# INPUT_POWER.net
KiCad netlist of a schematic drawn in Altium Designer
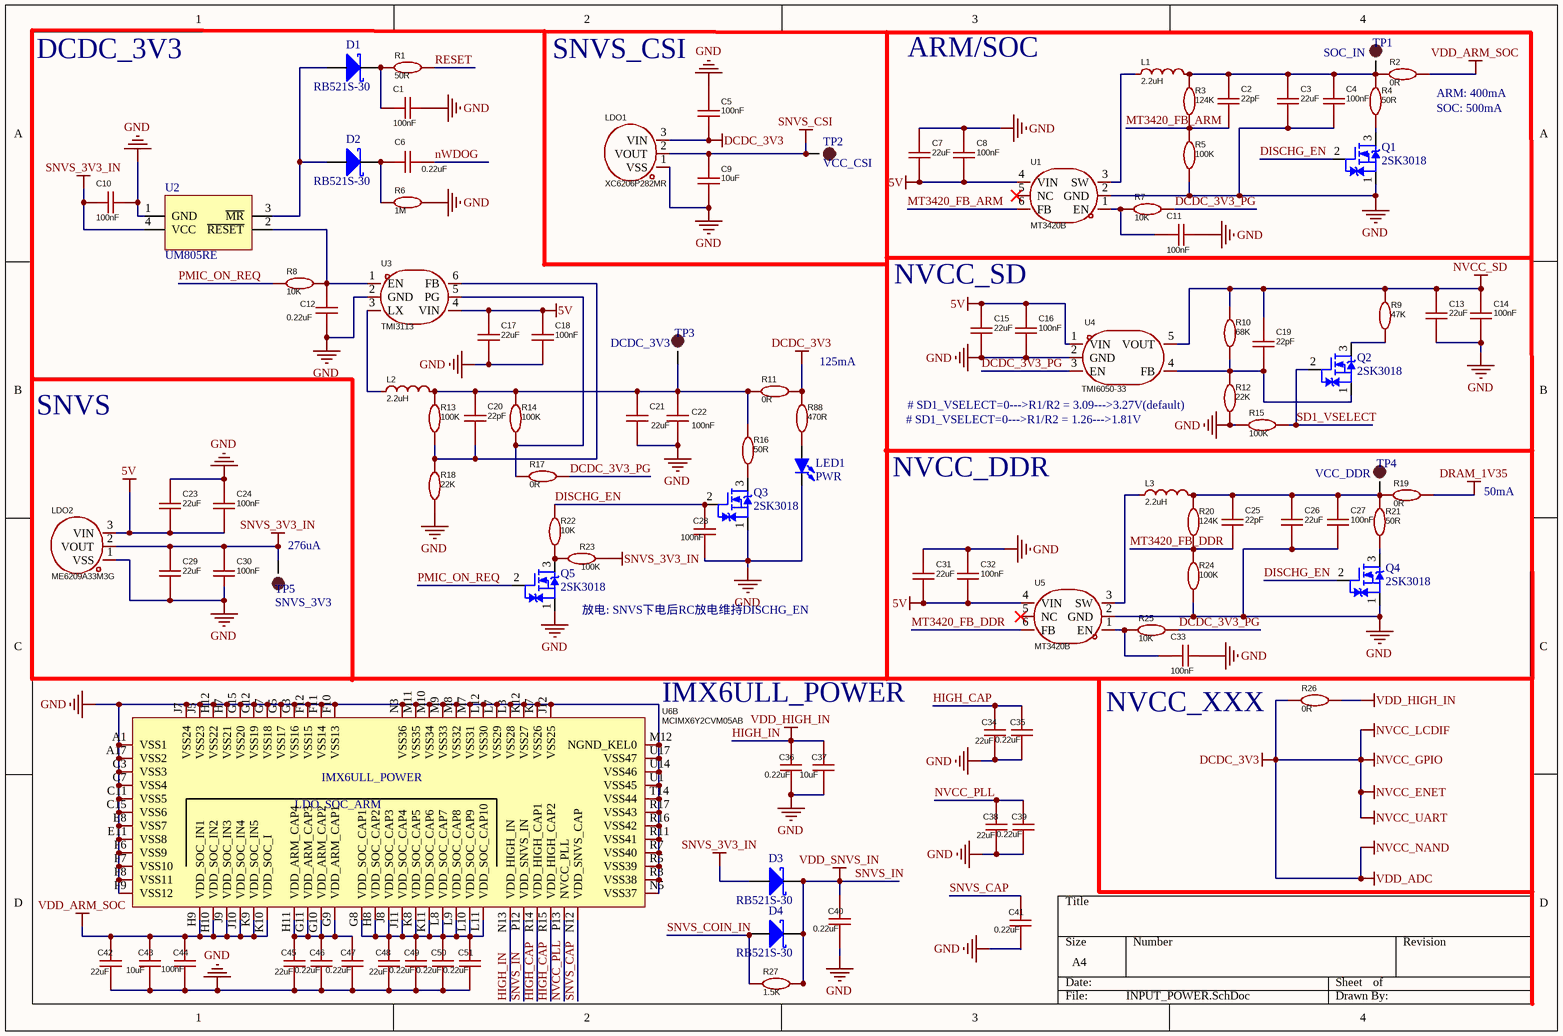
[diagram p0: INPUT_POWER.SchDoc]

(export (version "E")
  (design (tool "Eeschema 10.0.6"))
  (components
    (comp (ref "C1")
      (value "100nF")
      (footprint "PcbLib1:C0402")
      (description "容值:100nF;精度:±10%;额定电压:50V;材质(温度系数):X7R;")
      (fields
        (field (name "MANUFACTURER") "muRata(村田)")
        (field (name "MANUFACTURER PART") "GRM155R71H104KE14D")
      )
      (libsource (lib "Schlib1") (part "C0402"))
    )
    (comp (ref "C2")
      (value "22pF")
      (footprint "PcbLib1:C0402")
      (description "容值:100nF;精度:±10%;额定电压:50V;材质(温度系数):X7R;")
      (fields
        (field (name "MANUFACTURER") "muRata(村田)")
        (field (name "MANUFACTURER PART") "GRM155R71H104KE14D")
      )
      (libsource (lib "Schlib1") (part "C0402"))
    )
    (comp (ref "C3")
      (value "22uF")
      (footprint "PcbLib1:C0603")
      (description "容值:22uF;精度:±20%;额定电压:10V;材质(温度系数):X5R;")
      (fields
        (field (name "MANUFACTURER") "Chinocera(华瓷)")
        (field (name "MANUFACTURER PART") "HGC0603R5226M100NTHJ")
      )
      (libsource (lib "Schlib1") (part "C0603"))
    )
    (comp (ref "C4")
      (value "100nF")
      (footprint "PcbLib1:C0402")
      (description "容值:100nF;精度:±10%;额定电压:50V;材质(温度系数):X7R;")
      (fields
        (field (name "MANUFACTURER") "muRata(村田)")
        (field (name "MANUFACTURER PART") "GRM155R71H104KE14D")
      )
      (libsource (lib "Schlib1") (part "C0402"))
    )
    (comp (ref "C5")
      (value "100nF")
      (footprint "PcbLib1:C0402")
      (description "容值:100nF;精度:±10%;额定电压:50V;材质(温度系数):X7R;")
      (fields
        (field (name "MANUFACTURER") "muRata(村田)")
        (field (name "MANUFACTURER PART") "GRM155R71H104KE14D")
      )
      (libsource (lib "Schlib1") (part "C0402"))
    )
    (comp (ref "C6")
      (value "0.22uF")
      (footprint "PcbLib1:C0402")
      (description "容值:100nF;精度:±10%;额定电压:50V;材质(温度系数):X7R;")
      (fields
        (field (name "MANUFACTURER") "muRata(村田)")
        (field (name "MANUFACTURER PART") "GRM155R71H104KE14D")
      )
      (libsource (lib "Schlib1") (part "C0402"))
    )
    (comp (ref "C7")
      (value "22uF")
      (footprint "PcbLib1:C0603")
      (description "容值:22uF;精度:±20%;额定电压:10V;材质(温度系数):X5R;")
      (fields
        (field (name "MANUFACTURER") "Chinocera(华瓷)")
        (field (name "MANUFACTURER PART") "HGC0603R5226M100NTHJ")
      )
      (libsource (lib "Schlib1") (part "C0603"))
    )
    (comp (ref "C8")
      (value "100nF")
      (footprint "PcbLib1:C0402")
      (description "容值:100nF;精度:±10%;额定电压:50V;材质(温度系数):X7R;")
      (fields
        (field (name "MANUFACTURER") "muRata(村田)")
        (field (name "MANUFACTURER PART") "GRM155R71H104KE14D")
      )
      (libsource (lib "Schlib1") (part "C0402"))
    )
    (comp (ref "C9")
      (value "10uF")
      (footprint "PcbLib1:C0402")
      (description "容值:100nF;精度:±10%;额定电压:50V;材质(温度系数):X7R;")
      (fields
        (field (name "MANUFACTURER") "muRata(村田)")
        (field (name "MANUFACTURER PART") "GRM155R71H104KE14D")
      )
      (libsource (lib "Schlib1") (part "C0402"))
    )
    (comp (ref "C10")
      (value "100nF")
      (footprint "PcbLib1:C0402")
      (description "容值:100nF;精度:±10%;额定电压:50V;材质(温度系数):X7R;")
      (fields
        (field (name "MANUFACTURER") "muRata(村田)")
        (field (name "MANUFACTURER PART") "GRM155R71H104KE14D")
      )
      (libsource (lib "Schlib1") (part "C0402"))
    )
    (comp (ref "C11")
      (value "100nF")
      (footprint "PcbLib1:C0402")
      (description "容值:100nF;精度:±10%;额定电压:50V;材质(温度系数):X7R;")
      (fields
        (field (name "MANUFACTURER") "muRata(村田)")
        (field (name "MANUFACTURER PART") "GRM155R71H104KE14D")
      )
      (libsource (lib "Schlib1") (part "C0402"))
    )
    (comp (ref "C12")
      (value "0.22uF")
      (footprint "PcbLib1:C0402")
      (description "容值:100nF;精度:±10%;额定电压:50V;材质(温度系数):X7R;")
      (fields
        (field (name "MANUFACTURER") "muRata(村田)")
        (field (name "MANUFACTURER PART") "GRM155R71H104KE14D")
      )
      (libsource (lib "Schlib1") (part "C0402"))
    )
    (comp (ref "C13")
      (value "22uF")
      (footprint "PcbLib1:C0603")
      (description "容值:22uF;精度:±20%;额定电压:10V;材质(温度系数):X5R;")
      (fields
        (field (name "MANUFACTURER") "Chinocera(华瓷)")
        (field (name "MANUFACTURER PART") "HGC0603R5226M100NTHJ")
      )
      (libsource (lib "Schlib1") (part "C0603"))
    )
    (comp (ref "C14")
      (value "100nF")
      (footprint "PcbLib1:C0402")
      (description "容值:100nF;精度:±10%;额定电压:50V;材质(温度系数):X7R;")
      (fields
        (field (name "MANUFACTURER") "muRata(村田)")
        (field (name "MANUFACTURER PART") "GRM155R71H104KE14D")
      )
      (libsource (lib "Schlib1") (part "C0402"))
    )
    (comp (ref "C15")
      (value "22uF")
      (footprint "PcbLib1:C0603")
      (description "容值:22uF;精度:±20%;额定电压:10V;材质(温度系数):X5R;")
      (fields
        (field (name "MANUFACTURER") "Chinocera(华瓷)")
        (field (name "MANUFACTURER PART") "HGC0603R5226M100NTHJ")
      )
      (libsource (lib "Schlib1") (part "C0603"))
    )
    (comp (ref "C16")
      (value "100nF")
      (footprint "PcbLib1:C0402")
      (description "容值:100nF;精度:±10%;额定电压:50V;材质(温度系数):X7R;")
      (fields
        (field (name "MANUFACTURER") "muRata(村田)")
        (field (name "MANUFACTURER PART") "GRM155R71H104KE14D")
      )
      (libsource (lib "Schlib1") (part "C0402"))
    )
    (comp (ref "C17")
      (value "22uF")
      (footprint "PcbLib1:C0603")
      (description "容值:22uF;精度:±20%;额定电压:10V;材质(温度系数):X5R;")
      (fields
        (field (name "MANUFACTURER") "Chinocera(华瓷)")
        (field (name "MANUFACTURER PART") "HGC0603R5226M100NTHJ")
      )
      (libsource (lib "Schlib1") (part "C0603"))
    )
    (comp (ref "C18")
      (value "100nF")
      (footprint "PcbLib1:C0402")
      (description "容值:100nF;精度:±10%;额定电压:50V;材质(温度系数):X7R;")
      (fields
        (field (name "MANUFACTURER") "muRata(村田)")
        (field (name "MANUFACTURER PART") "GRM155R71H104KE14D")
      )
      (libsource (lib "Schlib1") (part "C0402"))
    )
    (comp (ref "C19")
      (value "22pF")
      (footprint "PcbLib1:C0402")
      (description "容值:100nF;精度:±10%;额定电压:50V;材质(温度系数):X7R;")
      (fields
        (field (name "MANUFACTURER") "muRata(村田)")
        (field (name "MANUFACTURER PART") "GRM155R71H104KE14D")
      )
      (libsource (lib "Schlib1") (part "C0402"))
    )
    (comp (ref "C20")
      (value "22pF")
      (footprint "PcbLib1:C0402")
      (description "容值:100nF;精度:±10%;额定电压:50V;材质(温度系数):X7R;")
      (fields
        (field (name "MANUFACTURER") "muRata(村田)")
        (field (name "MANUFACTURER PART") "GRM155R71H104KE14D")
      )
      (libsource (lib "Schlib1") (part "C0402"))
    )
    (comp (ref "C21")
      (value "22uF")
      (footprint "PcbLib1:C0603")
      (description "容值:22uF;精度:±20%;额定电压:10V;材质(温度系数):X5R;")
      (fields
        (field (name "MANUFACTURER") "Chinocera(华瓷)")
        (field (name "MANUFACTURER PART") "HGC0603R5226M100NTHJ")
      )
      (libsource (lib "Schlib1") (part "C0603"))
    )
    (comp (ref "C22")
      (value "100nF")
      (footprint "PcbLib1:C0402")
      (description "容值:100nF;精度:±10%;额定电压:50V;材质(温度系数):X7R;")
      (fields
        (field (name "MANUFACTURER") "muRata(村田)")
        (field (name "MANUFACTURER PART") "GRM155R71H104KE14D")
      )
      (libsource (lib "Schlib1") (part "C0402"))
    )
    (comp (ref "C23")
      (value "22uF")
      (footprint "PcbLib1:C0603")
      (description "容值:22uF;精度:±20%;额定电压:10V;材质(温度系数):X5R;")
      (fields
        (field (name "MANUFACTURER") "Chinocera(华瓷)")
        (field (name "MANUFACTURER PART") "HGC0603R5226M100NTHJ")
      )
      (libsource (lib "Schlib1") (part "C0603"))
    )
    (comp (ref "C24")
      (value "100nF")
      (footprint "PcbLib1:C0402")
      (description "容值:100nF;精度:±10%;额定电压:50V;材质(温度系数):X7R;")
      (fields
        (field (name "MANUFACTURER") "muRata(村田)")
        (field (name "MANUFACTURER PART") "GRM155R71H104KE14D")
      )
      (libsource (lib "Schlib1") (part "C0402"))
    )
    (comp (ref "C25")
      (value "22pF")
      (footprint "PcbLib1:C0402")
      (description "容值:100nF;精度:±10%;额定电压:50V;材质(温度系数):X7R;")
      (fields
        (field (name "MANUFACTURER") "muRata(村田)")
        (field (name "MANUFACTURER PART") "GRM155R71H104KE14D")
      )
      (libsource (lib "Schlib1") (part "C0402"))
    )
    (comp (ref "C26")
      (value "22uF")
      (footprint "PcbLib1:C0603")
      (description "容值:22uF;精度:±20%;额定电压:10V;材质(温度系数):X5R;")
      (fields
        (field (name "MANUFACTURER") "Chinocera(华瓷)")
        (field (name "MANUFACTURER PART") "HGC0603R5226M100NTHJ")
      )
      (libsource (lib "Schlib1") (part "C0603"))
    )
    (comp (ref "C27")
      (value "100nF")
      (footprint "PcbLib1:C0402")
      (description "容值:100nF;精度:±10%;额定电压:50V;材质(温度系数):X7R;")
      (fields
        (field (name "MANUFACTURER") "muRata(村田)")
        (field (name "MANUFACTURER PART") "GRM155R71H104KE14D")
      )
      (libsource (lib "Schlib1") (part "C0402"))
    )
    (comp (ref "C28")
      (value "100nF")
      (footprint "PcbLib1:C0402")
      (description "容值:100nF;精度:±10%;额定电压:50V;材质(温度系数):X7R;")
      (fields
        (field (name "MANUFACTURER") "muRata(村田)")
        (field (name "MANUFACTURER PART") "GRM155R71H104KE14D")
      )
      (libsource (lib "Schlib1") (part "C0402"))
    )
    (comp (ref "C29")
      (value "22uF")
      (footprint "PcbLib1:C0603")
      (description "容值:22uF;精度:±20%;额定电压:10V;材质(温度系数):X5R;")
      (fields
        (field (name "MANUFACTURER") "Chinocera(华瓷)")
        (field (name "MANUFACTURER PART") "HGC0603R5226M100NTHJ")
      )
      (libsource (lib "Schlib1") (part "C0603"))
    )
    (comp (ref "C30")
      (value "100nF")
      (footprint "PcbLib1:C0402")
      (description "容值:100nF;精度:±10%;额定电压:50V;材质(温度系数):X7R;")
      (fields
        (field (name "MANUFACTURER") "muRata(村田)")
        (field (name "MANUFACTURER PART") "GRM155R71H104KE14D")
      )
      (libsource (lib "Schlib1") (part "C0402"))
    )
    (comp (ref "C31")
      (value "22uF")
      (footprint "PcbLib1:C0603")
      (description "容值:22uF;精度:±20%;额定电压:10V;材质(温度系数):X5R;")
      (fields
        (field (name "MANUFACTURER") "Chinocera(华瓷)")
        (field (name "MANUFACTURER PART") "HGC0603R5226M100NTHJ")
      )
      (libsource (lib "Schlib1") (part "C0603"))
    )
    (comp (ref "C32")
      (value "100nF")
      (footprint "PcbLib1:C0402")
      (description "容值:100nF;精度:±10%;额定电压:50V;材质(温度系数):X7R;")
      (fields
        (field (name "MANUFACTURER") "muRata(村田)")
        (field (name "MANUFACTURER PART") "GRM155R71H104KE14D")
      )
      (libsource (lib "Schlib1") (part "C0402"))
    )
    (comp (ref "C33")
      (value "100nF")
      (footprint "PcbLib1:C0402")
      (description "容值:100nF;精度:±10%;额定电压:50V;材质(温度系数):X7R;")
      (fields
        (field (name "MANUFACTURER") "muRata(村田)")
        (field (name "MANUFACTURER PART") "GRM155R71H104KE14D")
      )
      (libsource (lib "Schlib1") (part "C0402"))
    )
    (comp (ref "C34")
      (value "22uF")
      (footprint "PcbLib1:C0603")
      (description "容值:22uF;精度:±20%;额定电压:10V;材质(温度系数):X5R;")
      (fields
        (field (name "MANUFACTURER") "Chinocera(华瓷)")
        (field (name "MANUFACTURER PART") "HGC0603R5226M100NTHJ")
      )
      (libsource (lib "Schlib1") (part "C0603"))
    )
    (comp (ref "C35")
      (value "0.22uF")
      (footprint "PcbLib1:C0402")
      (description "容值:100nF;精度:±10%;额定电压:50V;材质(温度系数):X7R;")
      (fields
        (field (name "MANUFACTURER") "muRata(村田)")
        (field (name "MANUFACTURER PART") "GRM155R71H104KE14D")
      )
      (libsource (lib "Schlib1") (part "C0402"))
    )
    (comp (ref "C36")
      (value "0.22uF")
      (footprint "PcbLib1:C0402")
      (description "容值:100nF;精度:±10%;额定电压:50V;材质(温度系数):X7R;")
      (fields
        (field (name "MANUFACTURER") "muRata(村田)")
        (field (name "MANUFACTURER PART") "GRM155R71H104KE14D")
      )
      (libsource (lib "Schlib1") (part "C0402"))
    )
    (comp (ref "C37")
      (value "10uF")
      (footprint "PcbLib1:C0402")
      (description "容值:100nF;精度:±10%;额定电压:50V;材质(温度系数):X7R;")
      (fields
        (field (name "MANUFACTURER") "muRata(村田)")
        (field (name "MANUFACTURER PART") "GRM155R71H104KE14D")
      )
      (libsource (lib "Schlib1") (part "C0402"))
    )
    (comp (ref "C38")
      (value "22uF")
      (footprint "PcbLib1:C0603")
      (description "容值:22uF;精度:±20%;额定电压:10V;材质(温度系数):X5R;")
      (fields
        (field (name "MANUFACTURER") "Chinocera(华瓷)")
        (field (name "MANUFACTURER PART") "HGC0603R5226M100NTHJ")
      )
      (libsource (lib "Schlib1") (part "C0603"))
    )
    (comp (ref "C39")
      (value "0.22uF")
      (footprint "PcbLib1:C0402")
      (description "容值:100nF;精度:±10%;额定电压:50V;材质(温度系数):X7R;")
      (fields
        (field (name "MANUFACTURER") "muRata(村田)")
        (field (name "MANUFACTURER PART") "GRM155R71H104KE14D")
      )
      (libsource (lib "Schlib1") (part "C0402"))
    )
    (comp (ref "C40")
      (value "0.22uF")
      (footprint "PcbLib1:C0402")
      (description "容值:100nF;精度:±10%;额定电压:50V;材质(温度系数):X7R;")
      (fields
        (field (name "MANUFACTURER") "muRata(村田)")
        (field (name "MANUFACTURER PART") "GRM155R71H104KE14D")
      )
      (libsource (lib "Schlib1") (part "C0402"))
    )
    (comp (ref "C41")
      (value "0.22uF")
      (footprint "PcbLib1:C0402")
      (description "容值:100nF;精度:±10%;额定电压:50V;材质(温度系数):X7R;")
      (fields
        (field (name "MANUFACTURER") "muRata(村田)")
        (field (name "MANUFACTURER PART") "GRM155R71H104KE14D")
      )
      (libsource (lib "Schlib1") (part "C0402"))
    )
    (comp (ref "C42")
      (value "22uF")
      (footprint "PcbLib1:C0603")
      (description "容值:22uF;精度:±20%;额定电压:10V;材质(温度系数):X5R;")
      (fields
        (field (name "MANUFACTURER") "Chinocera(华瓷)")
        (field (name "MANUFACTURER PART") "HGC0603R5226M100NTHJ")
      )
      (libsource (lib "Schlib1") (part "C0603"))
    )
    (comp (ref "C43")
      (value "10uF")
      (footprint "PcbLib1:C0402")
      (description "容值:100nF;精度:±10%;额定电压:50V;材质(温度系数):X7R;")
      (fields
        (field (name "MANUFACTURER") "muRata(村田)")
        (field (name "MANUFACTURER PART") "GRM155R71H104KE14D")
      )
      (libsource (lib "Schlib1") (part "C0402"))
    )
    (comp (ref "C44")
      (value "100nF")
      (footprint "PcbLib1:C0402")
      (description "容值:100nF;精度:±10%;额定电压:50V;材质(温度系数):X7R;")
      (fields
        (field (name "MANUFACTURER") "muRata(村田)")
        (field (name "MANUFACTURER PART") "GRM155R71H104KE14D")
      )
      (libsource (lib "Schlib1") (part "C0402"))
    )
    (comp (ref "C45")
      (value "22uF")
      (footprint "PcbLib1:C0603")
      (description "容值:22uF;精度:±20%;额定电压:10V;材质(温度系数):X5R;")
      (fields
        (field (name "MANUFACTURER") "Chinocera(华瓷)")
        (field (name "MANUFACTURER PART") "HGC0603R5226M100NTHJ")
      )
      (libsource (lib "Schlib1") (part "C0603"))
    )
    (comp (ref "C46")
      (value "0.22uF")
      (footprint "PcbLib1:C0402")
      (description "容值:100nF;精度:±10%;额定电压:50V;材质(温度系数):X7R;")
      (fields
        (field (name "MANUFACTURER") "muRata(村田)")
        (field (name "MANUFACTURER PART") "GRM155R71H104KE14D")
      )
      (libsource (lib "Schlib1") (part "C0402"))
    )
    (comp (ref "C47")
      (value "0.22uF")
      (footprint "PcbLib1:C0402")
      (description "容值:100nF;精度:±10%;额定电压:50V;材质(温度系数):X7R;")
      (fields
        (field (name "MANUFACTURER") "muRata(村田)")
        (field (name "MANUFACTURER PART") "GRM155R71H104KE14D")
      )
      (libsource (lib "Schlib1") (part "C0402"))
    )
    (comp (ref "C48")
      (value "22uF")
      (footprint "PcbLib1:C0603")
      (description "容值:22uF;精度:±20%;额定电压:10V;材质(温度系数):X5R;")
      (fields
        (field (name "MANUFACTURER") "Chinocera(华瓷)")
        (field (name "MANUFACTURER PART") "HGC0603R5226M100NTHJ")
      )
      (libsource (lib "Schlib1") (part "C0603"))
    )
    (comp (ref "C49")
      (value "0.22uF")
      (footprint "PcbLib1:C0402")
      (description "容值:100nF;精度:±10%;额定电压:50V;材质(温度系数):X7R;")
      (fields
        (field (name "MANUFACTURER") "muRata(村田)")
        (field (name "MANUFACTURER PART") "GRM155R71H104KE14D")
      )
      (libsource (lib "Schlib1") (part "C0402"))
    )
    (comp (ref "C50")
      (value "0.22uF")
      (footprint "PcbLib1:C0402")
      (description "容值:100nF;精度:±10%;额定电压:50V;材质(温度系数):X7R;")
      (fields
        (field (name "MANUFACTURER") "muRata(村田)")
        (field (name "MANUFACTURER PART") "GRM155R71H104KE14D")
      )
      (libsource (lib "Schlib1") (part "C0402"))
    )
    (comp (ref "C51")
      (value "0.22uF")
      (footprint "PcbLib1:C0402")
      (description "容值:100nF;精度:±10%;额定电压:50V;材质(温度系数):X7R;")
      (fields
        (field (name "MANUFACTURER") "muRata(村田)")
        (field (name "MANUFACTURER PART") "GRM155R71H104KE14D")
      )
      (libsource (lib "Schlib1") (part "C0402"))
    )
    (comp (ref "D1") (value "RB521S-30") (footprint "SOD-523") (libsource (lib "Schlib1") (part "RB521S-30")))
    (comp (ref "D2") (value "RB521S-30") (footprint "SOD-523") (libsource (lib "Schlib1") (part "RB521S-30")))
    (comp (ref "D3") (value "RB521S-30") (footprint "SOD-523") (libsource (lib "Schlib1") (part "RB521S-30")))
    (comp (ref "D4") (value "RB521S-30") (footprint "SOD-523") (libsource (lib "Schlib1") (part "RB521S-30")))
    (comp (ref "L1")
      (value "2.2uH")
      (footprint "PcbLib1:IND-SMD_L2.5-W2.0_MHCHL2520")
      (description "电感值:2.2uH;精度:±20%;额定电流:3A;饱和电流(Isat):3.8A;类型:一体成型电感;")
      (fields
        (field (name "MANUFACTURER") "cjiang(长江微电)")
        (field (name "MANUFACTURER PART") "FTC252012S2R2MBCA")
      )
      (libsource (lib "Schlib1") (part "L2.5_SMD"))
    )
    (comp (ref "L2")
      (value "2.2uH")
      (footprint "PcbLib1:IND-SMD_L2.5-W2.0_MHCHL2520")
      (description "电感值:2.2uH;精度:±20%;额定电流:3A;饱和电流(Isat):3.8A;类型:一体成型电感;")
      (fields
        (field (name "MANUFACTURER") "cjiang(长江微电)")
        (field (name "MANUFACTURER PART") "FTC252012S2R2MBCA")
      )
      (libsource (lib "Schlib1") (part "L2.5_SMD"))
    )
    (comp (ref "L3")
      (value "2.2uH")
      (footprint "PcbLib1:IND-SMD_L2.5-W2.0_MHCHL2520")
      (description "电感值:2.2uH;精度:±20%;额定电流:3A;饱和电流(Isat):3.8A;类型:一体成型电感;")
      (fields
        (field (name "MANUFACTURER") "cjiang(长江微电)")
        (field (name "MANUFACTURER PART") "FTC252012S2R2MBCA")
      )
      (libsource (lib "Schlib1") (part "L2.5_SMD"))
    )
    (comp (ref "LDO1")
      (value "XC6206P282MR")
      (footprint "PcbLib1:SOT-23-3_L2.9-W1.6-P1.90-LS2.8-BR")
      (description "输出类型:固定;最大输入电压:6V;输出电压:3.3V;最大输出电流:250mA;电源纹波抑制比(PSRR):-;输出极性:正极;")
      (fields (field (name "MANUFACTURER") "MICRONE(南京微盟)") (field (name "MANUFACTURER PART") "ME6209A33M3G"))
      (libsource (lib "Schlib1") (part "XC6206P282MR"))
    )
    (comp (ref "LDO2")
      (value "ME6209A33M3G")
      (footprint "PcbLib1:SOT-23-3_L2.9-W1.6-P1.90-LS2.8-BR")
      (description "输出类型:固定;最大输入电压:18V;输出电压:3.3V;最大输出电流:250mA;电源纹波抑制比(PSRR):-;输出极性:正极;")
      (fields (field (name "MANUFACTURER") "MICRONE(南京微盟)"))
      (libsource (lib "Schlib1") (part "ME6209A33M3G"))
    )
    (comp (ref "LED1")
      (value "PWR")
      (footprint "PcbLib1:LED 0603B")
      (description "贴片LED")
      (fields (field (name "版权归属") "源创客"))
      (libsource (lib "Schlib1") (part "LED-SMD"))
    )
    (comp (ref "Q1")
      (value "2SK3018")
      (footprint "SOT:SC70-3N")
      (description "N沟场效应管  30V,0.1A")
      (fields (field (name "版权归属") "源创客"))
      (libsource (lib "Schlib1") (part "2SK3018"))
    )
    (comp (ref "Q2")
      (value "2SK3018")
      (footprint "SOT:SC70-3N")
      (description "N沟场效应管  30V,0.1A")
      (fields (field (name "版权归属") "源创客"))
      (libsource (lib "Schlib1") (part "2SK3018"))
    )
    (comp (ref "Q3")
      (value "2SK3018")
      (footprint "SOT:SC70-3N")
      (description "N沟场效应管  30V,0.1A")
      (fields (field (name "版权归属") "源创客"))
      (libsource (lib "Schlib1") (part "2SK3018"))
    )
    (comp (ref "Q4")
      (value "2SK3018")
      (footprint "SOT:SC70-3N")
      (description "N沟场效应管  30V,0.1A")
      (fields (field (name "版权归属") "源创客"))
      (libsource (lib "Schlib1") (part "2SK3018"))
    )
    (comp (ref "Q5")
      (value "2SK3018")
      (footprint "SOT:SC70-3N")
      (description "N沟场效应管  30V,0.1A")
      (fields (field (name "版权归属") "源创客"))
      (libsource (lib "Schlib1") (part "2SK3018"))
    )
    (comp (ref "R1")
      (value "50R")
      (footprint "PcbLib1:R0402")
      (description "电阻类型:厚膜电阻;阻值:1kΩ;精度:±1%;功率:62.5mW;最大工作电压:50V;温度系数:±100ppm/℃;")
      (fields
        (field (name "MANUFACTURER") "UNI-ROYAL(厚声)")
        (field (name "MANUFACTURER PART") "0402WGF1001TCE")
      )
      (libsource (lib "Schlib1") (part "R0402"))
    )
    (comp (ref "R2")
      (value "0R")
      (footprint "PcbLib1:R0402")
      (description "电阻类型:厚膜电阻;阻值:1kΩ;精度:±1%;功率:62.5mW;最大工作电压:50V;温度系数:±100ppm/℃;")
      (fields
        (field (name "MANUFACTURER") "UNI-ROYAL(厚声)")
        (field (name "MANUFACTURER PART") "0402WGF1001TCE")
      )
      (libsource (lib "Schlib1") (part "R0402"))
    )
    (comp (ref "R3")
      (value "124K")
      (footprint "PcbLib1:R0402")
      (description "电阻类型:厚膜电阻;阻值:1kΩ;精度:±1%;功率:62.5mW;最大工作电压:50V;温度系数:±100ppm/℃;")
      (fields
        (field (name "MANUFACTURER") "UNI-ROYAL(厚声)")
        (field (name "MANUFACTURER PART") "0402WGF1001TCE")
      )
      (libsource (lib "Schlib1") (part "R0402"))
    )
    (comp (ref "R4")
      (value "50R")
      (footprint "PcbLib1:R0402")
      (description "电阻类型:厚膜电阻;阻值:1kΩ;精度:±1%;功率:62.5mW;最大工作电压:50V;温度系数:±100ppm/℃;")
      (fields
        (field (name "MANUFACTURER") "UNI-ROYAL(厚声)")
        (field (name "MANUFACTURER PART") "0402WGF1001TCE")
      )
      (libsource (lib "Schlib1") (part "R0402"))
    )
    (comp (ref "R5")
      (value "100K")
      (footprint "PcbLib1:R0402")
      (description "电阻类型:厚膜电阻;阻值:1kΩ;精度:±1%;功率:62.5mW;最大工作电压:50V;温度系数:±100ppm/℃;")
      (fields
        (field (name "MANUFACTURER") "UNI-ROYAL(厚声)")
        (field (name "MANUFACTURER PART") "0402WGF1001TCE")
      )
      (libsource (lib "Schlib1") (part "R0402"))
    )
    (comp (ref "R6")
      (value "1M")
      (footprint "PcbLib1:R0402")
      (description "电阻类型:厚膜电阻;阻值:1kΩ;精度:±1%;功率:62.5mW;最大工作电压:50V;温度系数:±100ppm/℃;")
      (fields
        (field (name "MANUFACTURER") "UNI-ROYAL(厚声)")
        (field (name "MANUFACTURER PART") "0402WGF1001TCE")
      )
      (libsource (lib "Schlib1") (part "R0402"))
    )
    (comp (ref "R7")
      (value "10K")
      (footprint "PcbLib1:R0402")
      (description "电阻类型:厚膜电阻;阻值:1kΩ;精度:±1%;功率:62.5mW;最大工作电压:50V;温度系数:±100ppm/℃;")
      (fields
        (field (name "MANUFACTURER") "UNI-ROYAL(厚声)")
        (field (name "MANUFACTURER PART") "0402WGF1001TCE")
      )
      (libsource (lib "Schlib1") (part "R0402"))
    )
    (comp (ref "R8")
      (value "10K")
      (footprint "PcbLib1:R0402")
      (description "电阻类型:厚膜电阻;阻值:1kΩ;精度:±1%;功率:62.5mW;最大工作电压:50V;温度系数:±100ppm/℃;")
      (fields
        (field (name "MANUFACTURER") "UNI-ROYAL(厚声)")
        (field (name "MANUFACTURER PART") "0402WGF1001TCE")
      )
      (libsource (lib "Schlib1") (part "R0402"))
    )
    (comp (ref "R9")
      (value "47K")
      (footprint "PcbLib1:R0402")
      (description "电阻类型:厚膜电阻;阻值:1kΩ;精度:±1%;功率:62.5mW;最大工作电压:50V;温度系数:±100ppm/℃;")
      (fields
        (field (name "MANUFACTURER") "UNI-ROYAL(厚声)")
        (field (name "MANUFACTURER PART") "0402WGF1001TCE")
      )
      (libsource (lib "Schlib1") (part "R0402"))
    )
    (comp (ref "R10")
      (value "68K")
      (footprint "PcbLib1:R0402")
      (description "电阻类型:厚膜电阻;阻值:1kΩ;精度:±1%;功率:62.5mW;最大工作电压:50V;温度系数:±100ppm/℃;")
      (fields
        (field (name "MANUFACTURER") "UNI-ROYAL(厚声)")
        (field (name "MANUFACTURER PART") "0402WGF1001TCE")
      )
      (libsource (lib "Schlib1") (part "R0402"))
    )
    (comp (ref "R11")
      (value "0R")
      (footprint "PcbLib1:R0402")
      (description "电阻类型:厚膜电阻;阻值:1kΩ;精度:±1%;功率:62.5mW;最大工作电压:50V;温度系数:±100ppm/℃;")
      (fields
        (field (name "MANUFACTURER") "UNI-ROYAL(厚声)")
        (field (name "MANUFACTURER PART") "0402WGF1001TCE")
      )
      (libsource (lib "Schlib1") (part "R0402"))
    )
    (comp (ref "R12")
      (value "22K")
      (footprint "PcbLib1:R0402")
      (description "电阻类型:厚膜电阻;阻值:1kΩ;精度:±1%;功率:62.5mW;最大工作电压:50V;温度系数:±100ppm/℃;")
      (fields
        (field (name "MANUFACTURER") "UNI-ROYAL(厚声)")
        (field (name "MANUFACTURER PART") "0402WGF1001TCE")
      )
      (libsource (lib "Schlib1") (part "R0402"))
    )
    (comp (ref "R13")
      (value "100K")
      (footprint "PcbLib1:R0402")
      (description "电阻类型:厚膜电阻;阻值:1kΩ;精度:±1%;功率:62.5mW;最大工作电压:50V;温度系数:±100ppm/℃;")
      (fields
        (field (name "MANUFACTURER") "UNI-ROYAL(厚声)")
        (field (name "MANUFACTURER PART") "0402WGF1001TCE")
      )
      (libsource (lib "Schlib1") (part "R0402"))
    )
    (comp (ref "R14")
      (value "100K")
      (footprint "PcbLib1:R0402")
      (description "电阻类型:厚膜电阻;阻值:1kΩ;精度:±1%;功率:62.5mW;最大工作电压:50V;温度系数:±100ppm/℃;")
      (fields
        (field (name "MANUFACTURER") "UNI-ROYAL(厚声)")
        (field (name "MANUFACTURER PART") "0402WGF1001TCE")
      )
      (libsource (lib "Schlib1") (part "R0402"))
    )
    (comp (ref "R15")
      (value "100K")
      (footprint "PcbLib1:R0402")
      (description "电阻类型:厚膜电阻;阻值:1kΩ;精度:±1%;功率:62.5mW;最大工作电压:50V;温度系数:±100ppm/℃;")
      (fields
        (field (name "MANUFACTURER") "UNI-ROYAL(厚声)")
        (field (name "MANUFACTURER PART") "0402WGF1001TCE")
      )
      (libsource (lib "Schlib1") (part "R0402"))
    )
    (comp (ref "R16")
      (value "50R")
      (footprint "PcbLib1:R0402")
      (description "电阻类型:厚膜电阻;阻值:1kΩ;精度:±1%;功率:62.5mW;最大工作电压:50V;温度系数:±100ppm/℃;")
      (fields
        (field (name "MANUFACTURER") "UNI-ROYAL(厚声)")
        (field (name "MANUFACTURER PART") "0402WGF1001TCE")
      )
      (libsource (lib "Schlib1") (part "R0402"))
    )
    (comp (ref "R17")
      (value "0R")
      (footprint "PcbLib1:R0402")
      (description "电阻类型:厚膜电阻;阻值:1kΩ;精度:±1%;功率:62.5mW;最大工作电压:50V;温度系数:±100ppm/℃;")
      (fields
        (field (name "MANUFACTURER") "UNI-ROYAL(厚声)")
        (field (name "MANUFACTURER PART") "0402WGF1001TCE")
      )
      (libsource (lib "Schlib1") (part "R0402"))
    )
    (comp (ref "R18")
      (value "22K")
      (footprint "PcbLib1:R0402")
      (description "电阻类型:厚膜电阻;阻值:1kΩ;精度:±1%;功率:62.5mW;最大工作电压:50V;温度系数:±100ppm/℃;")
      (fields
        (field (name "MANUFACTURER") "UNI-ROYAL(厚声)")
        (field (name "MANUFACTURER PART") "0402WGF1001TCE")
      )
      (libsource (lib "Schlib1") (part "R0402"))
    )
    (comp (ref "R19")
      (value "0R")
      (footprint "PcbLib1:R0402")
      (description "电阻类型:厚膜电阻;阻值:1kΩ;精度:±1%;功率:62.5mW;最大工作电压:50V;温度系数:±100ppm/℃;")
      (fields
        (field (name "MANUFACTURER") "UNI-ROYAL(厚声)")
        (field (name "MANUFACTURER PART") "0402WGF1001TCE")
      )
      (libsource (lib "Schlib1") (part "R0402"))
    )
    (comp (ref "R20")
      (value "124K")
      (footprint "PcbLib1:R0402")
      (description "电阻类型:厚膜电阻;阻值:1kΩ;精度:±1%;功率:62.5mW;最大工作电压:50V;温度系数:±100ppm/℃;")
      (fields
        (field (name "MANUFACTURER") "UNI-ROYAL(厚声)")
        (field (name "MANUFACTURER PART") "0402WGF1001TCE")
      )
      (libsource (lib "Schlib1") (part "R0402"))
    )
    (comp (ref "R21")
      (value "50R")
      (footprint "PcbLib1:R0402")
      (description "电阻类型:厚膜电阻;阻值:1kΩ;精度:±1%;功率:62.5mW;最大工作电压:50V;温度系数:±100ppm/℃;")
      (fields
        (field (name "MANUFACTURER") "UNI-ROYAL(厚声)")
        (field (name "MANUFACTURER PART") "0402WGF1001TCE")
      )
      (libsource (lib "Schlib1") (part "R0402"))
    )
    (comp (ref "R22")
      (value "10K")
      (footprint "PcbLib1:R0402")
      (description "电阻类型:厚膜电阻;阻值:1kΩ;精度:±1%;功率:62.5mW;最大工作电压:50V;温度系数:±100ppm/℃;")
      (fields
        (field (name "MANUFACTURER") "UNI-ROYAL(厚声)")
        (field (name "MANUFACTURER PART") "0402WGF1001TCE")
      )
      (libsource (lib "Schlib1") (part "R0402"))
    )
    (comp (ref "R23")
      (value "100K")
      (footprint "PcbLib1:R0402")
      (description "电阻类型:厚膜电阻;阻值:1kΩ;精度:±1%;功率:62.5mW;最大工作电压:50V;温度系数:±100ppm/℃;")
      (fields
        (field (name "MANUFACTURER") "UNI-ROYAL(厚声)")
        (field (name "MANUFACTURER PART") "0402WGF1001TCE")
      )
      (libsource (lib "Schlib1") (part "R0402"))
    )
    (comp (ref "R24")
      (value "100K")
      (footprint "PcbLib1:R0402")
      (description "电阻类型:厚膜电阻;阻值:1kΩ;精度:±1%;功率:62.5mW;最大工作电压:50V;温度系数:±100ppm/℃;")
      (fields
        (field (name "MANUFACTURER") "UNI-ROYAL(厚声)")
        (field (name "MANUFACTURER PART") "0402WGF1001TCE")
      )
      (libsource (lib "Schlib1") (part "R0402"))
    )
    (comp (ref "R25")
      (value "10K")
      (footprint "PcbLib1:R0402")
      (description "电阻类型:厚膜电阻;阻值:1kΩ;精度:±1%;功率:62.5mW;最大工作电压:50V;温度系数:±100ppm/℃;")
      (fields
        (field (name "MANUFACTURER") "UNI-ROYAL(厚声)")
        (field (name "MANUFACTURER PART") "0402WGF1001TCE")
      )
      (libsource (lib "Schlib1") (part "R0402"))
    )
    (comp (ref "R26")
      (value "0R")
      (footprint "PcbLib1:R0402")
      (description "电阻类型:厚膜电阻;阻值:1kΩ;精度:±1%;功率:62.5mW;最大工作电压:50V;温度系数:±100ppm/℃;")
      (fields
        (field (name "MANUFACTURER") "UNI-ROYAL(厚声)")
        (field (name "MANUFACTURER PART") "0402WGF1001TCE")
      )
      (libsource (lib "Schlib1") (part "R0402"))
    )
    (comp (ref "R27")
      (value "1.5K")
      (footprint "PcbLib1:R0402")
      (description "电阻类型:厚膜电阻;阻值:1kΩ;精度:±1%;功率:62.5mW;最大工作电压:50V;温度系数:±100ppm/℃;")
      (fields
        (field (name "MANUFACTURER") "UNI-ROYAL(厚声)")
        (field (name "MANUFACTURER PART") "0402WGF1001TCE")
      )
      (libsource (lib "Schlib1") (part "R0402"))
    )
    (comp (ref "R88")
      (value "470R")
      (footprint "PcbLib1:R0402")
      (description "电阻类型:厚膜电阻;阻值:1kΩ;精度:±1%;功率:62.5mW;最大工作电压:50V;温度系数:±100ppm/℃;")
      (fields
        (field (name "MANUFACTURER") "UNI-ROYAL(厚声)")
        (field (name "MANUFACTURER PART") "0402WGF1001TCE")
      )
      (libsource (lib "Schlib1") (part "R0402"))
    )
    (comp (ref "TP1")
      (value "SOC_IN")
      (footprint "TP-1.0")
      (description "测试点")
      (libsource (lib "Schlib1") (part "TEST-POINT"))
    )
    (comp (ref "TP2")
      (value "VCC_CSI")
      (footprint "TP-1.0")
      (description "测试点")
      (libsource (lib "Schlib1") (part "TEST-POINT"))
    )
    (comp (ref "TP3")
      (value "DCDC_3V3")
      (footprint "TP-1.0")
      (description "测试点")
      (libsource (lib "Schlib1") (part "TEST-POINT"))
    )
    (comp (ref "TP4")
      (value "VCC_DDR")
      (footprint "TP-1.0")
      (description "测试点")
      (libsource (lib "Schlib1") (part "TEST-POINT"))
    )
    (comp (ref "TP5")
      (value "SNVS_3V3")
      (footprint "TP-1.0")
      (description "测试点")
      (libsource (lib "Schlib1") (part "TEST-POINT"))
    )
    (comp (ref "U1")
      (value "MT3420B")
      (footprint "PcbLib1:SOT-23-6_L2.9-W1.6-P0.95-LS2.8-BL")
      (description "功能类型:降压型;输出类型:可调;输入电压:2.3V~6V;输出电流:2A;")
      (fields (field (name "MANUFACTURER") "西安航天民芯"))
      (libsource (lib "Schlib1") (part "MT3420B"))
    )
    (comp (ref "U2") (value "UM805RE") (footprint "SOT143") (libsource (lib "Schlib1") (part "UM805RE")))
    (comp (ref "U3")
      (value "TMI3113")
      (footprint "PcbLib1:SOT-23-6_L2.9-W1.6-P0.95-LS2.8-BL")
      (fields (field (name "MANUFACTURER") "TMI(拓尔微)"))
      (libsource (lib "Schlib1") (part "TMI3113"))
    )
    (comp (ref "U4")
      (value "TMI6050-33")
      (footprint "PcbLib1:SOT-23-5_L2.9-W1.6-P0.95-LS2.8-BR")
      (description "输出类型:-;")
      (fields (field (name "MANUFACTURER") "TMI(拓尔微)"))
      (libsource (lib "Schlib1") (part "TMI6050-33"))
    )
    (comp (ref "U5")
      (value "MT3420B")
      (footprint "PcbLib1:SOT-23-6_L2.9-W1.6-P0.95-LS2.8-BL")
      (description "功能类型:降压型;输出类型:可调;输入电压:2.3V~6V;输出电流:2A;")
      (fields (field (name "MANUFACTURER") "西安航天民芯"))
      (libsource (lib "Schlib1") (part "MT3420B"))
    )
    (comp (ref "U6")
      (value "MCIMX6Y2CVM05AB")
      (footprint "PcbLib1:BGA-289_L14.0-W14.0-R17-C17-P0.80-BL")
      (description "CPU内核:ARM-A系列;RAM总容量:128KB;GPIO端口数量:-;工作电压范围:-;CPU最大主频:528MHz;程序存储器类型:-;应用领域:-;")
      (fields (field (name "MANUFACTURER") "NXP(恩智浦)"))
      (libsource (lib "Schlib1") (part "MCIMX6Y2CVM05AB"))
    )
  )
  (nets
    (net (code "1") (name "/DCDC_3V3_PG") (class "Default")
      (node (ref "R17") (pin "2") (pinfunction "2_2") (pintype "passive"))
      (node (ref "R25") (pin "1") (pinfunction "1_1") (pintype "passive"))
      (node (ref "R7") (pin "1") (pinfunction "1_1") (pintype "passive"))
      (node (ref "U4") (pin "3") (pinfunction "EN_3") (pintype "passive"))
    )
    (net (code "2") (name "/DISCHG_EN") (class "Default")
      (node (ref "C28") (pin "2") (pinfunction "2_2") (pintype "passive"))
      (node (ref "Q1") (pin "2") (pinfunction "G_2") (pintype "passive"))
      (node (ref "Q3") (pin "2") (pinfunction "G_2") (pintype "passive"))
      (node (ref "Q4") (pin "2") (pinfunction "G_2") (pintype "passive"))
      (node (ref "R22") (pin "2") (pinfunction "2_2") (pintype "passive"))
    )
    (net (code "3") (name "/HIGH_CAP") (class "Default")
      (node (ref "C34") (pin "2") (pinfunction "2_2") (pintype "passive"))
      (node (ref "C35") (pin "2") (pinfunction "2_2") (pintype "passive"))
      (node (ref "U6") (pin "R14") (pinfunction "VDD_HIGH_CAP1_R14") (pintype "passive"))
      (node (ref "U6") (pin "R15") (pinfunction "VDD_HIGH_CAP2_R15") (pintype "passive"))
    )
    (net (code "4") (name "/MT3420_FB_ARM") (class "Default")
      (node (ref "C2") (pin "1") (pinfunction "1_1") (pintype "passive"))
      (node (ref "R3") (pin "2") (pinfunction "2_2") (pintype "passive"))
      (node (ref "R5") (pin "1") (pinfunction "1_1") (pintype "passive"))
      (node (ref "U1") (pin "6") (pinfunction "FB_6") (pintype "passive"))
    )
    (net (code "5") (name "/MT3420_FB_DDR") (class "Default")
      (node (ref "C25") (pin "1") (pinfunction "1_1") (pintype "passive"))
      (node (ref "R20") (pin "2") (pinfunction "2_2") (pintype "passive"))
      (node (ref "R24") (pin "1") (pinfunction "1_1") (pintype "passive"))
      (node (ref "U5") (pin "6") (pinfunction "FB_6") (pintype "passive"))
    )
    (net (code "6") (name "/NVCC_PLL") (class "Default")
      (node (ref "C38") (pin "2") (pinfunction "2_2") (pintype "passive"))
      (node (ref "C39") (pin "2") (pinfunction "2_2") (pintype "passive"))
      (node (ref "U6") (pin "P13") (pinfunction "NVCC_PLL_P13") (pintype "passive"))
    )
    (net (code "7") (name "/PMIC_ON_REQ") (class "Default")
      (node (ref "Q5") (pin "2") (pinfunction "G_2") (pintype "passive"))
      (node (ref "R8") (pin "1") (pinfunction "1_1") (pintype "passive"))
    )
    (net (code "8") (name "/RESET") (class "Default")
      (node (ref "R1") (pin "2") (pinfunction "2_2") (pintype "passive"))
    )
    (net (code "9") (name "/SD1_VSELECT") (class "Default")
      (node (ref "Q2") (pin "2") (pinfunction "G_2") (pintype "passive"))
      (node (ref "R15") (pin "2") (pinfunction "2_2") (pintype "passive"))
    )
    (net (code "10") (name "/SNVS_CAP") (class "Default")
      (node (ref "C41") (pin "2") (pinfunction "2_2") (pintype "passive"))
      (node (ref "U6") (pin "N12") (pinfunction "VDD_SNVS_CAP_N12") (pintype "passive"))
    )
    (net (code "11") (name "/SNVS_COIN_IN") (class "Default")
      (node (ref "D4") (pin "1") (pinfunction "A_1") (pintype "passive"))
      (node (ref "R27") (pin "2") (pinfunction "2_2") (pintype "passive"))
    )
    (net (code "12") (name "/nWDOG") (class "Default")
      (node (ref "C6") (pin "1") (pinfunction "1_1") (pintype "passive"))
    )
    (net (code "13") (name "5V") (class "Default")
      (node (ref "C15") (pin "2") (pinfunction "2_2") (pintype "passive"))
      (node (ref "C16") (pin "2") (pinfunction "2_2") (pintype "passive"))
      (node (ref "C17") (pin "2") (pinfunction "2_2") (pintype "passive"))
      (node (ref "C18") (pin "2") (pinfunction "2_2") (pintype "passive"))
      (node (ref "C23") (pin "1") (pinfunction "1_1") (pintype "passive"))
      (node (ref "C24") (pin "1") (pinfunction "1_1") (pintype "passive"))
      (node (ref "C31") (pin "1") (pinfunction "1_1") (pintype "passive"))
      (node (ref "C32") (pin "1") (pinfunction "1_1") (pintype "passive"))
      (node (ref "C7") (pin "1") (pinfunction "1_1") (pintype "passive"))
      (node (ref "C8") (pin "1") (pinfunction "1_1") (pintype "passive"))
      (node (ref "LDO2") (pin "3") (pinfunction "VIN_3") (pintype "passive"))
      (node (ref "U1") (pin "4") (pinfunction "VIN_4") (pintype "passive"))
      (node (ref "U3") (pin "4") (pinfunction "VIN_4") (pintype "passive"))
      (node (ref "U4") (pin "1") (pinfunction "VIN_1") (pintype "passive"))
      (node (ref "U5") (pin "4") (pinfunction "VIN_4") (pintype "passive"))
    )
    (net (code "14") (name "DCDC_3V3") (class "Default")
      (node (ref "C5") (pin "2") (pinfunction "2_2") (pintype "passive"))
      (node (ref "LDO1") (pin "3") (pinfunction "VIN_3") (pintype "passive"))
      (node (ref "R11") (pin "2") (pinfunction "2_2") (pintype "passive"))
      (node (ref "R26") (pin "1") (pinfunction "1_1") (pintype "passive"))
      (node (ref "R88") (pin "2") (pinfunction "2_2") (pintype "passive"))
    )
    (net (code "15") (name "DRAM_1V35") (class "Default")
      (node (ref "R19") (pin "2") (pinfunction "2_2") (pintype "passive"))
    )
    (net (code "16") (name "GND") (class "Default")
      (node (ref "C1") (pin "1") (pinfunction "1_1") (pintype "passive"))
      (node (ref "C10") (pin "1") (pinfunction "1_1") (pintype "passive"))
      (node (ref "C11") (pin "1") (pinfunction "1_1") (pintype "passive"))
      (node (ref "C12") (pin "2") (pinfunction "2_2") (pintype "passive"))
      (node (ref "C13") (pin "1") (pinfunction "1_1") (pintype "passive"))
      (node (ref "C14") (pin "1") (pinfunction "1_1") (pintype "passive"))
      (node (ref "C15") (pin "1") (pinfunction "1_1") (pintype "passive"))
      (node (ref "C16") (pin "1") (pinfunction "1_1") (pintype "passive"))
      (node (ref "C17") (pin "1") (pinfunction "1_1") (pintype "passive"))
      (node (ref "C18") (pin "1") (pinfunction "1_1") (pintype "passive"))
      (node (ref "C21") (pin "1") (pinfunction "1_1") (pintype "passive"))
      (node (ref "C22") (pin "1") (pinfunction "1_1") (pintype "passive"))
      (node (ref "C23") (pin "2") (pinfunction "2_2") (pintype "passive"))
      (node (ref "C24") (pin "2") (pinfunction "2_2") (pintype "passive"))
      (node (ref "C26") (pin "1") (pinfunction "1_1") (pintype "passive"))
      (node (ref "C27") (pin "1") (pinfunction "1_1") (pintype "passive"))
      (node (ref "C28") (pin "1") (pinfunction "1_1") (pintype "passive"))
      (node (ref "C29") (pin "1") (pinfunction "1_1") (pintype "passive"))
      (node (ref "C3") (pin "1") (pinfunction "1_1") (pintype "passive"))
      (node (ref "C30") (pin "1") (pinfunction "1_1") (pintype "passive"))
      (node (ref "C31") (pin "2") (pinfunction "2_2") (pintype "passive"))
      (node (ref "C32") (pin "2") (pinfunction "2_2") (pintype "passive"))
      (node (ref "C33") (pin "1") (pinfunction "1_1") (pintype "passive"))
      (node (ref "C34") (pin "1") (pinfunction "1_1") (pintype "passive"))
      (node (ref "C35") (pin "1") (pinfunction "1_1") (pintype "passive"))
      (node (ref "C36") (pin "1") (pinfunction "1_1") (pintype "passive"))
      (node (ref "C37") (pin "1") (pinfunction "1_1") (pintype "passive"))
      (node (ref "C38") (pin "1") (pinfunction "1_1") (pintype "passive"))
      (node (ref "C39") (pin "1") (pinfunction "1_1") (pintype "passive"))
      (node (ref "C4") (pin "1") (pinfunction "1_1") (pintype "passive"))
      (node (ref "C40") (pin "1") (pinfunction "1_1") (pintype "passive"))
      (node (ref "C41") (pin "1") (pinfunction "1_1") (pintype "passive"))
      (node (ref "C42") (pin "1") (pinfunction "1_1") (pintype "passive"))
      (node (ref "C43") (pin "1") (pinfunction "1_1") (pintype "passive"))
      (node (ref "C44") (pin "1") (pinfunction "1_1") (pintype "passive"))
      (node (ref "C45") (pin "1") (pinfunction "1_1") (pintype "passive"))
      (node (ref "C46") (pin "1") (pinfunction "1_1") (pintype "passive"))
      (node (ref "C47") (pin "1") (pinfunction "1_1") (pintype "passive"))
      (node (ref "C48") (pin "1") (pinfunction "1_1") (pintype "passive"))
      (node (ref "C49") (pin "1") (pinfunction "1_1") (pintype "passive"))
      (node (ref "C5") (pin "1") (pinfunction "1_1") (pintype "passive"))
      (node (ref "C50") (pin "1") (pinfunction "1_1") (pintype "passive"))
      (node (ref "C51") (pin "1") (pinfunction "1_1") (pintype "passive"))
      (node (ref "C7") (pin "2") (pinfunction "2_2") (pintype "passive"))
      (node (ref "C8") (pin "2") (pinfunction "2_2") (pintype "passive"))
      (node (ref "C9") (pin "1") (pinfunction "1_1") (pintype "passive"))
      (node (ref "LDO1") (pin "1") (pinfunction "VSS_1") (pintype "passive"))
      (node (ref "LDO2") (pin "1") (pinfunction "VSS_1") (pintype "passive"))
      (node (ref "LED1") (pin "2") (pinfunction "K_2") (pintype "passive"))
      (node (ref "Q1") (pin "1") (pinfunction "S_1") (pintype "passive"))
      (node (ref "Q3") (pin "1") (pinfunction "S_1") (pintype "passive"))
      (node (ref "Q4") (pin "1") (pinfunction "S_1") (pintype "passive"))
      (node (ref "Q5") (pin "1") (pinfunction "S_1") (pintype "passive"))
      (node (ref "R12") (pin "2") (pinfunction "2_2") (pintype "passive"))
      (node (ref "R15") (pin "1") (pinfunction "1_1") (pintype "passive"))
      (node (ref "R18") (pin "1") (pinfunction "1_1") (pintype "passive"))
      (node (ref "R24") (pin "2") (pinfunction "2_2") (pintype "passive"))
      (node (ref "R5") (pin "2") (pinfunction "2_2") (pintype "passive"))
      (node (ref "R6") (pin "2") (pinfunction "2_2") (pintype "passive"))
      (node (ref "U1") (pin "2") (pinfunction "GND_2") (pintype "passive"))
      (node (ref "U2") (pin "1") (pinfunction "GND_1") (pintype "passive"))
      (node (ref "U3") (pin "2") (pinfunction "GND_2") (pintype "passive"))
      (node (ref "U4") (pin "2") (pinfunction "GND_2") (pintype "passive"))
      (node (ref "U5") (pin "2") (pinfunction "GND_2") (pintype "passive"))
      (node (ref "U6") (pin "A1") (pinfunction "VSS1_A1") (pintype "passive"))
      (node (ref "U6") (pin "A17") (pinfunction "VSS2_A17") (pintype "passive"))
      (node (ref "U6") (pin "C11") (pinfunction "VSS5_C11") (pintype "passive"))
      (node (ref "U6") (pin "C15") (pinfunction "VSS6_C15") (pintype "passive"))
      (node (ref "U6") (pin "C3") (pinfunction "VSS3_C3") (pintype "passive"))
      (node (ref "U6") (pin "C7") (pinfunction "VSS4_C7") (pintype "passive"))
      (node (ref "U6") (pin "E11") (pinfunction "VSS8_E11") (pintype "passive"))
      (node (ref "U6") (pin "E8") (pinfunction "VSS7_E8") (pintype "passive"))
      (node (ref "U6") (pin "F10") (pinfunction "VSS13_F10") (pintype "passive"))
      (node (ref "U6") (pin "F11") (pinfunction "VSS14_F11") (pintype "passive"))
      (node (ref "U6") (pin "F12") (pinfunction "VSS15_F12") (pintype "passive"))
      (node (ref "U6") (pin "F6") (pinfunction "VSS9_F6") (pintype "passive"))
      (node (ref "U6") (pin "F7") (pinfunction "VSS10_F7") (pintype "passive"))
      (node (ref "U6") (pin "F8") (pinfunction "VSS11_F8") (pintype "passive"))
      (node (ref "U6") (pin "F9") (pinfunction "VSS12_F9") (pintype "passive"))
      (node (ref "U6") (pin "G12") (pinfunction "VSS19_G12") (pintype "passive"))
      (node (ref "U6") (pin "G15") (pinfunction "VSS20_G15") (pintype "passive"))
      (node (ref "U6") (pin "G3") (pinfunction "VSS16_G3") (pintype "passive"))
      (node (ref "U6") (pin "G5") (pinfunction "VSS17_G5") (pintype "passive"))
      (node (ref "U6") (pin "G7") (pinfunction "VSS18_G7") (pintype "passive"))
      (node (ref "U6") (pin "H12") (pinfunction "VSS22_H12") (pintype "passive"))
      (node (ref "U6") (pin "H7") (pinfunction "VSS21_H7") (pintype "passive"))
      (node (ref "U6") (pin "J12") (pinfunction "VSS25_J12") (pintype "passive"))
      (node (ref "U6") (pin "J5") (pinfunction "VSS23_J5") (pintype "passive"))
      (node (ref "U6") (pin "J7") (pinfunction "VSS24_J7") (pintype "passive"))
      (node (ref "U6") (pin "K12") (pinfunction "VSS27_K12") (pintype "passive"))
      (node (ref "U6") (pin "K7") (pinfunction "VSS26_K7") (pintype "passive"))
      (node (ref "U6") (pin "L12") (pinfunction "VSS30_L12") (pintype "passive"))
      (node (ref "U6") (pin "L3") (pinfunction "VSS28_L3") (pintype "passive"))
      (node (ref "U6") (pin "L7") (pinfunction "VSS29_L7") (pintype "passive"))
      (node (ref "U6") (pin "M10") (pinfunction "VSS34_M10") (pintype "passive"))
      (node (ref "U6") (pin "M11") (pinfunction "VSS35_M11") (pintype "passive"))
      (node (ref "U6") (pin "M12") (pinfunction "NGND_KEL0_M12") (pintype "passive"))
      (node (ref "U6") (pin "M7") (pinfunction "VSS31_M7") (pintype "passive"))
      (node (ref "U6") (pin "M8") (pinfunction "VSS32_M8") (pintype "passive"))
      (node (ref "U6") (pin "M9") (pinfunction "VSS33_M9") (pintype "passive"))
      (node (ref "U6") (pin "N3") (pinfunction "VSS36_N3") (pintype "passive"))
      (node (ref "U6") (pin "N5") (pinfunction "VSS37_N5") (pintype "passive"))
      (node (ref "U6") (pin "R11") (pinfunction "VSS41_R11") (pintype "passive"))
      (node (ref "U6") (pin "R16") (pinfunction "VSS42_R16") (pintype "passive"))
      (node (ref "U6") (pin "R17") (pinfunction "VSS43_R17") (pintype "passive"))
      (node (ref "U6") (pin "R3") (pinfunction "VSS38_R3") (pintype "passive"))
      (node (ref "U6") (pin "R5") (pinfunction "VSS39_R5") (pintype "passive"))
      (node (ref "U6") (pin "R7") (pinfunction "VSS40_R7") (pintype "passive"))
      (node (ref "U6") (pin "T14") (pinfunction "VSS44_T14") (pintype "passive"))
      (node (ref "U6") (pin "U1") (pinfunction "VSS45_U1") (pintype "passive"))
      (node (ref "U6") (pin "U14") (pinfunction "VSS46_U14") (pintype "passive"))
      (node (ref "U6") (pin "U17") (pinfunction "VSS47_U17") (pintype "passive"))
    )
    (net (code "17") (name "NVCC_SD") (class "Default")
      (node (ref "C13") (pin "2") (pinfunction "2_2") (pintype "passive"))
      (node (ref "C14") (pin "2") (pinfunction "2_2") (pintype "passive"))
      (node (ref "C19") (pin "2") (pinfunction "2_2") (pintype "passive"))
      (node (ref "R10") (pin "1") (pinfunction "1_1") (pintype "passive"))
      (node (ref "R9") (pin "2") (pinfunction "2_2") (pintype "passive"))
      (node (ref "U4") (pin "5") (pinfunction "VOUT_5") (pintype "passive"))
    )
    (net (code "18") (name "Net-(C2-Pad2)") (class "Default")
      (node (ref "C2") (pin "2") (pinfunction "2_2") (pintype "passive"))
      (node (ref "C3") (pin "2") (pinfunction "2_2") (pintype "passive"))
      (node (ref "C4") (pin "2") (pinfunction "2_2") (pintype "passive"))
      (node (ref "L1") (pin "2") (pinfunction "2_2") (pintype "passive"))
      (node (ref "R2") (pin "1") (pinfunction "1_1") (pintype "passive"))
      (node (ref "R3") (pin "1") (pinfunction "1_1") (pintype "passive"))
      (node (ref "R4") (pin "2") (pinfunction "2_2") (pintype "passive"))
      (node (ref "TP1") (pin "1") (pinfunction "1_1") (pintype "passive"))
    )
    (net (code "19") (name "Net-(C20-Pad1)") (class "Default")
      (node (ref "C20") (pin "1") (pinfunction "1_1") (pintype "passive"))
      (node (ref "C21") (pin "2") (pinfunction "2_2") (pintype "passive"))
      (node (ref "C22") (pin "2") (pinfunction "2_2") (pintype "passive"))
      (node (ref "L2") (pin "2") (pinfunction "2_2") (pintype "passive"))
      (node (ref "R11") (pin "1") (pinfunction "1_1") (pintype "passive"))
      (node (ref "R13") (pin "2") (pinfunction "2_2") (pintype "passive"))
      (node (ref "R14") (pin "1") (pinfunction "1_1") (pintype "passive"))
      (node (ref "R16") (pin "2") (pinfunction "2_2") (pintype "passive"))
      (node (ref "TP3") (pin "1") (pinfunction "1_1") (pintype "passive"))
    )
    (net (code "20") (name "Net-(C25-Pad2)") (class "Default")
      (node (ref "C25") (pin "2") (pinfunction "2_2") (pintype "passive"))
      (node (ref "C26") (pin "2") (pinfunction "2_2") (pintype "passive"))
      (node (ref "C27") (pin "2") (pinfunction "2_2") (pintype "passive"))
      (node (ref "L3") (pin "2") (pinfunction "2_2") (pintype "passive"))
      (node (ref "R19") (pin "1") (pinfunction "1_1") (pintype "passive"))
      (node (ref "R20") (pin "1") (pinfunction "1_1") (pintype "passive"))
      (node (ref "R21") (pin "2") (pinfunction "2_2") (pintype "passive"))
      (node (ref "TP4") (pin "1") (pinfunction "1_1") (pintype "passive"))
    )
    (net (code "21") (name "Net-(D1-A)") (class "Default")
      (node (ref "D1") (pin "1") (pinfunction "A_1") (pintype "passive"))
      (node (ref "D2") (pin "1") (pinfunction "A_1") (pintype "passive"))
      (node (ref "U2") (pin "3") (pinfunction "~{MR}_3") (pintype "passive"))
    )
    (net (code "22") (name "Net-(D1-C)") (class "Default")
      (node (ref "C1") (pin "2") (pinfunction "2_2") (pintype "passive"))
      (node (ref "D1") (pin "2") (pinfunction "C_2") (pintype "passive"))
      (node (ref "R1") (pin "1") (pinfunction "1_1") (pintype "passive"))
    )
    (net (code "23") (name "Net-(D2-C)") (class "Default")
      (node (ref "C6") (pin "2") (pinfunction "2_2") (pintype "passive"))
      (node (ref "D2") (pin "2") (pinfunction "C_2") (pintype "passive"))
      (node (ref "R6") (pin "1") (pinfunction "1_1") (pintype "passive"))
    )
    (net (code "24") (name "Net-(LED1-A)") (class "Default")
      (node (ref "LED1") (pin "1") (pinfunction "A_1") (pintype "passive"))
      (node (ref "R88") (pin "1") (pinfunction "1_1") (pintype "passive"))
    )
    (net (code "25") (name "Net-(Q1-D)") (class "Default")
      (node (ref "Q1") (pin "3") (pinfunction "D_3") (pintype "passive"))
      (node (ref "R4") (pin "1") (pinfunction "1_1") (pintype "passive"))
    )
    (net (code "26") (name "Net-(Q2-D)") (class "Default")
      (node (ref "Q2") (pin "3") (pinfunction "D_3") (pintype "passive"))
      (node (ref "R9") (pin "1") (pinfunction "1_1") (pintype "passive"))
    )
    (net (code "27") (name "Net-(Q2-S)") (class "Default")
      (node (ref "C19") (pin "1") (pinfunction "1_1") (pintype "passive"))
      (node (ref "Q2") (pin "1") (pinfunction "S_1") (pintype "passive"))
      (node (ref "R10") (pin "2") (pinfunction "2_2") (pintype "passive"))
      (node (ref "R12") (pin "1") (pinfunction "1_1") (pintype "passive"))
      (node (ref "U4") (pin "4") (pinfunction "FB_4") (pintype "passive"))
    )
    (net (code "28") (name "Net-(Q3-D)") (class "Default")
      (node (ref "Q3") (pin "3") (pinfunction "D_3") (pintype "passive"))
      (node (ref "R16") (pin "1") (pinfunction "1_1") (pintype "passive"))
    )
    (net (code "29") (name "Net-(Q4-D)") (class "Default")
      (node (ref "Q4") (pin "3") (pinfunction "D_3") (pintype "passive"))
      (node (ref "R21") (pin "1") (pinfunction "1_1") (pintype "passive"))
    )
    (net (code "30") (name "Net-(Q5-D)") (class "Default")
      (node (ref "Q5") (pin "3") (pinfunction "D_3") (pintype "passive"))
      (node (ref "R22") (pin "1") (pinfunction "1_1") (pintype "passive"))
      (node (ref "R23") (pin "2") (pinfunction "2_2") (pintype "passive"))
    )
    (net (code "31") (name "Net-(U1-EN)") (class "Default")
      (node (ref "C11") (pin "2") (pinfunction "2_2") (pintype "passive"))
      (node (ref "R7") (pin "2") (pinfunction "2_2") (pintype "passive"))
      (node (ref "U1") (pin "1") (pinfunction "EN_1") (pintype "passive"))
    )
    (net (code "32") (name "Net-(U1-SW)") (class "Default")
      (node (ref "L1") (pin "1") (pinfunction "1_1") (pintype "passive"))
      (node (ref "U1") (pin "3") (pinfunction "SW_3") (pintype "passive"))
    )
    (net (code "33") (name "Net-(U2-~{RESET})") (class "Default")
      (node (ref "C12") (pin "1") (pinfunction "1_1") (pintype "passive"))
      (node (ref "R8") (pin "2") (pinfunction "2_2") (pintype "passive"))
      (node (ref "U2") (pin "2") (pinfunction "~{RESET}_2") (pintype "passive"))
      (node (ref "U3") (pin "1") (pinfunction "EN_1") (pintype "passive"))
    )
    (net (code "34") (name "Net-(U3-FB)") (class "Default")
      (node (ref "C20") (pin "2") (pinfunction "2_2") (pintype "passive"))
      (node (ref "R13") (pin "1") (pinfunction "1_1") (pintype "passive"))
      (node (ref "R18") (pin "2") (pinfunction "2_2") (pintype "passive"))
      (node (ref "U3") (pin "6") (pinfunction "FB_6") (pintype "passive"))
    )
    (net (code "35") (name "Net-(U3-LX)") (class "Default")
      (node (ref "L2") (pin "1") (pinfunction "1_1") (pintype "passive"))
      (node (ref "U3") (pin "3") (pinfunction "LX_3") (pintype "passive"))
    )
    (net (code "36") (name "Net-(U3-PG)") (class "Default")
      (node (ref "R14") (pin "2") (pinfunction "2_2") (pintype "passive"))
      (node (ref "R17") (pin "1") (pinfunction "1_1") (pintype "passive"))
      (node (ref "U3") (pin "5") (pinfunction "PG_5") (pintype "passive"))
    )
    (net (code "37") (name "Net-(U5-EN)") (class "Default")
      (node (ref "C33") (pin "2") (pinfunction "2_2") (pintype "passive"))
      (node (ref "R25") (pin "2") (pinfunction "2_2") (pintype "passive"))
      (node (ref "U5") (pin "1") (pinfunction "EN_1") (pintype "passive"))
    )
    (net (code "38") (name "Net-(U5-SW)") (class "Default")
      (node (ref "L3") (pin "1") (pinfunction "1_1") (pintype "passive"))
      (node (ref "U5") (pin "3") (pinfunction "SW_3") (pintype "passive"))
    )
    (net (code "39") (name "Net-(U6B-VDD_ARM_CAP1)") (class "Default")
      (node (ref "C45") (pin "2") (pinfunction "2_2") (pintype "passive"))
      (node (ref "C46") (pin "2") (pinfunction "2_2") (pintype "passive"))
      (node (ref "C47") (pin "2") (pinfunction "2_2") (pintype "passive"))
      (node (ref "U6") (pin "G10") (pinfunction "VDD_ARM_CAP2_G10") (pintype "passive"))
      (node (ref "U6") (pin "G11") (pinfunction "VDD_ARM_CAP3_G11") (pintype "passive"))
      (node (ref "U6") (pin "G9") (pinfunction "VDD_ARM_CAP1_G9") (pintype "passive"))
      (node (ref "U6") (pin "H11") (pinfunction "VDD_ARM_CAP4_H11") (pintype "passive"))
    )
    (net (code "40") (name "Net-(U6B-VDD_SOC_CAP1)") (class "Default")
      (node (ref "C48") (pin "2") (pinfunction "2_2") (pintype "passive"))
      (node (ref "C49") (pin "2") (pinfunction "2_2") (pintype "passive"))
      (node (ref "C50") (pin "2") (pinfunction "2_2") (pintype "passive"))
      (node (ref "C51") (pin "2") (pinfunction "2_2") (pintype "passive"))
      (node (ref "U6") (pin "G8") (pinfunction "VDD_SOC_CAP1_G8") (pintype "passive"))
      (node (ref "U6") (pin "H8") (pinfunction "VDD_SOC_CAP2_H8") (pintype "passive"))
      (node (ref "U6") (pin "J11") (pinfunction "VDD_SOC_CAP4_J11") (pintype "passive"))
      (node (ref "U6") (pin "J8") (pinfunction "VDD_SOC_CAP3_J8") (pintype "passive"))
      (node (ref "U6") (pin "K11") (pinfunction "VDD_SOC_CAP6_K11") (pintype "passive"))
      (node (ref "U6") (pin "K8") (pinfunction "VDD_SOC_CAP5_K8") (pintype "passive"))
      (node (ref "U6") (pin "L10") (pinfunction "VDD_SOC_CAP9_L10") (pintype "passive"))
      (node (ref "U6") (pin "L11") (pinfunction "VDD_SOC_CAP10_L11") (pintype "passive"))
      (node (ref "U6") (pin "L8") (pinfunction "VDD_SOC_CAP7_L8") (pintype "passive"))
      (node (ref "U6") (pin "L9") (pinfunction "VDD_SOC_CAP8_L9") (pintype "passive"))
    )
    (net (code "41") (name "SNVS_3V3_IN") (class "Default")
      (node (ref "C10") (pin "2") (pinfunction "2_2") (pintype "passive"))
      (node (ref "C29") (pin "2") (pinfunction "2_2") (pintype "passive"))
      (node (ref "C30") (pin "2") (pinfunction "2_2") (pintype "passive"))
      (node (ref "D3") (pin "1") (pinfunction "A_1") (pintype "passive"))
      (node (ref "LDO2") (pin "2") (pinfunction "VOUT_2") (pintype "passive"))
      (node (ref "R23") (pin "1") (pinfunction "1_1") (pintype "passive"))
      (node (ref "TP5") (pin "1") (pinfunction "1_1") (pintype "passive"))
      (node (ref "U2") (pin "4") (pinfunction "VCC_4") (pintype "passive"))
    )
    (net (code "42") (name "SNVS_CSI") (class "Default")
      (node (ref "C9") (pin "2") (pinfunction "2_2") (pintype "passive"))
      (node (ref "LDO1") (pin "2") (pinfunction "VOUT_2") (pintype "passive"))
      (node (ref "TP2") (pin "1") (pinfunction "1_1") (pintype "passive"))
    )
    (net (code "43") (name "VDD_ARM_SOC") (class "Default")
      (node (ref "C42") (pin "2") (pinfunction "2_2") (pintype "passive"))
      (node (ref "C43") (pin "2") (pinfunction "2_2") (pintype "passive"))
      (node (ref "C44") (pin "2") (pinfunction "2_2") (pintype "passive"))
      (node (ref "R2") (pin "2") (pinfunction "2_2") (pintype "passive"))
      (node (ref "U6") (pin "H10") (pinfunction "VDD_SOC_IN2_H10") (pintype "passive"))
      (node (ref "U6") (pin "H9") (pinfunction "VDD_SOC_IN1_H9") (pintype "passive"))
      (node (ref "U6") (pin "J10") (pinfunction "VDD_SOC_IN4_J10") (pintype "passive"))
      (node (ref "U6") (pin "J9") (pinfunction "VDD_SOC_IN3_J9") (pintype "passive"))
      (node (ref "U6") (pin "K10") (pinfunction "VDD_SOC_I_K10") (pintype "passive"))
      (node (ref "U6") (pin "K9") (pinfunction "VDD_SOC_IN5_K9") (pintype "passive"))
    )
    (net (code "44") (name "VDD_HIGH_IN") (class "Default")
      (node (ref "C36") (pin "2") (pinfunction "2_2") (pintype "passive"))
      (node (ref "C37") (pin "2") (pinfunction "2_2") (pintype "passive"))
      (node (ref "R26") (pin "2") (pinfunction "2_2") (pintype "passive"))
      (node (ref "U6") (pin "N13") (pinfunction "VDD_HIGH_IN_N13") (pintype "passive"))
    )
    (net (code "45") (name "VDD_SNVS_IN") (class "Default")
      (node (ref "C40") (pin "2") (pinfunction "2_2") (pintype "passive"))
      (node (ref "D3") (pin "2") (pinfunction "C_2") (pintype "passive"))
      (node (ref "D4") (pin "2") (pinfunction "C_2") (pintype "passive"))
      (node (ref "R27") (pin "1") (pinfunction "1_1") (pintype "passive"))
      (node (ref "U6") (pin "P12") (pinfunction "VDD_SNVS_IN_P12") (pintype "passive"))
    )
    (net (code "46") (name "unconnected-(U1-NC-Pad5)") (class "Default")
      (node (ref "U1") (pin "5") (pinfunction "NC_5") (pintype "passive+no_connect"))
    )
    (net (code "47") (name "unconnected-(U5-NC-Pad5)") (class "Default")
      (node (ref "U5") (pin "5") (pinfunction "NC_5") (pintype "passive+no_connect"))
    )
  )
)
